# Uno_trung_tam_nha_kinh.net
KiCad netlist of a schematic drawn in Altium Designer
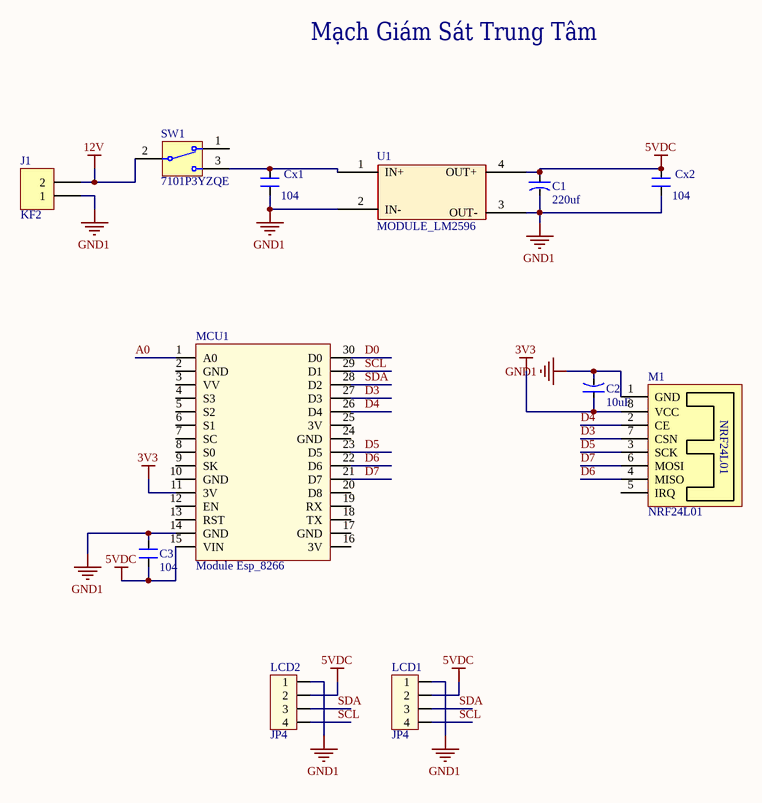
[diagram p0: Uno trung tam nha kinh.SchDoc]

(export (version "E")
  (design (tool "Eeschema 10.0.6"))
  (components
    (comp (ref "C1")
      (value "220uf")
      (footprint "CA-ALU-10R")
      (description "Capacitor (Semiconductor SIM Model)")
      (fields (field (name "PUBLISHER") "Altium Limited"))
      (libsource (lib "LIBRARY") (part "CN-ALU-DIP"))
    )
    (comp (ref "C2")
      (value "10uF")
      (footprint "CA-ALU-6.3R")
      (description "Capacitor (Semiconductor SIM Model)")
      (fields (field (name "PUBLISHER") "Altium Limited"))
      (libsource (lib "LIBRARY") (part "CN-ALU-DIP"))
    )
    (comp (ref "C3") (value "104") (footprint "CN2-T") (libsource (lib "LIBRARY") (part "CN")))
    (comp (ref "Cx1") (value "104") (footprint "CN2-T") (libsource (lib "LIBRARY") (part "CN")))
    (comp (ref "Cx2") (value "104") (footprint "CN2-T") (libsource (lib "LIBRARY") (part "CN")))
    (comp (ref "J1")
      (value "KF2")
      (footprint "KF2-5.08")
      (fields
        (field (name "MANUFACTURER") "Würth Elektronik eiSos GmbH")
        (field (name "PARTNO") "691103110002")
        (field (name "CREATED BY") "Karrer Zheng")
      )
      (libsource (lib "LIBRARY") (part "KF2"))
    )
    (comp (ref "LCD1")
      (value "JP4")
      (footprint "CON4")
      (description "Connector 4")
      (libsource (lib "syhaunguyen") (part "Con4"))
    )
    (comp (ref "LCD2")
      (value "JP4")
      (footprint "CON4")
      (description "Connector 4")
      (libsource (lib "syhaunguyen") (part "Con4"))
    )
    (comp (ref "M1") (value "NRF24L01") (footprint "NRF24L01") (libsource (lib "LIBRARY") (part "NRF24L01")))
    (comp (ref "MCU1")
      (value "Module Esp_8266")
      (footprint "BaDinh_Library:Esp8266_NodeMCU_CP2102")
      (libsource (lib "BaDinh_Library") (part "Module Esp_8266"))
    )
    (comp (ref "SW1")
      (value "7101P3YZQE")
      (footprint "SW_TOGGLE_7101P3YZQE")
      (description "SWITCH TOGGLE SPDT 5A 120V")
      (fields (field (name "MANUFACTURER") "C&K"))
      (libsource (lib "Indruino") (part "SW_TOGGLE_7101P3YZQE"))
    )
    (comp (ref "U1")
      (value "MODULE_LM2596")
      (footprint "BaDinh_Library:MODULE_LM2596")
      (libsource (lib "BaDinh_Library") (part "MODULE_LM2596"))
    )
  )
  (nets
    (net (code "1") (name "/A0") (class "Default")
      (node (ref "MCU1") (pin "1") (pinfunction "A0_1") (pintype "passive"))
    )
    (net (code "2") (name "/D0") (class "Default")
      (node (ref "MCU1") (pin "30") (pinfunction "D0_30") (pintype "passive"))
    )
    (net (code "3") (name "/D3") (class "Default")
      (node (ref "M1") (pin "7") (pinfunction "CSN_7") (pintype "passive"))
      (node (ref "MCU1") (pin "27") (pinfunction "D3_27") (pintype "passive"))
    )
    (net (code "4") (name "/D4") (class "Default")
      (node (ref "M1") (pin "2") (pinfunction "CE_2") (pintype "passive"))
      (node (ref "MCU1") (pin "26") (pinfunction "D4_26") (pintype "passive"))
    )
    (net (code "5") (name "/D5") (class "Default")
      (node (ref "M1") (pin "3") (pinfunction "SCK_3") (pintype "passive"))
      (node (ref "MCU1") (pin "23") (pinfunction "D5_23") (pintype "passive"))
    )
    (net (code "6") (name "/D6") (class "Default")
      (node (ref "M1") (pin "4") (pinfunction "MISO_4") (pintype "passive"))
      (node (ref "MCU1") (pin "22") (pinfunction "D6_22") (pintype "passive"))
    )
    (net (code "7") (name "/D7") (class "Default")
      (node (ref "M1") (pin "6") (pinfunction "MOSI_6") (pintype "passive"))
      (node (ref "MCU1") (pin "21") (pinfunction "D7_21") (pintype "passive"))
    )
    (net (code "8") (name "/SCL") (class "Default")
      (node (ref "LCD1") (pin "4") (pinfunction "4_4") (pintype "passive"))
      (node (ref "LCD2") (pin "4") (pinfunction "4_4") (pintype "passive"))
      (node (ref "MCU1") (pin "29") (pinfunction "D1_29") (pintype "passive"))
    )
    (net (code "9") (name "/SDA") (class "Default")
      (node (ref "LCD1") (pin "3") (pinfunction "3_3") (pintype "passive"))
      (node (ref "LCD2") (pin "3") (pinfunction "3_3") (pintype "passive"))
      (node (ref "MCU1") (pin "28") (pinfunction "D2_28") (pintype "passive"))
    )
    (net (code "10") (name "3V3") (class "Default")
      (node (ref "C2") (pin "1") (pinfunction "1_1") (pintype "passive"))
      (node (ref "M1") (pin "8") (pinfunction "VCC_8") (pintype "passive"))
      (node (ref "MCU1") (pin "11") (pinfunction "3V_11") (pintype "passive"))
    )
    (net (code "11") (name "5VDC") (class "Default")
      (node (ref "C1") (pin "1") (pinfunction "1_1") (pintype "passive"))
      (node (ref "C3") (pin "1") (pinfunction "1_1") (pintype "passive"))
      (node (ref "Cx2") (pin "2") (pinfunction "2_2") (pintype "passive"))
      (node (ref "LCD1") (pin "2") (pinfunction "2_2") (pintype "passive"))
      (node (ref "LCD2") (pin "2") (pinfunction "2_2") (pintype "passive"))
      (node (ref "MCU1") (pin "15") (pinfunction "VIN_15") (pintype "passive"))
      (node (ref "U1") (pin "4") (pinfunction "OUT+_4") (pintype "passive"))
    )
    (net (code "12") (name "12V") (class "Default")
      (node (ref "J1") (pin "2") (pinfunction "2_2") (pintype "passive"))
      (node (ref "SW1") (pin "2") (pinfunction "COM_2") (pintype "passive"))
    )
    (net (code "13") (name "GND1") (class "Default")
      (node (ref "C1") (pin "2") (pinfunction "2_2") (pintype "passive"))
      (node (ref "C2") (pin "2") (pinfunction "2_2") (pintype "passive"))
      (node (ref "C3") (pin "2") (pinfunction "2_2") (pintype "passive"))
      (node (ref "Cx1") (pin "1") (pinfunction "1_1") (pintype "passive"))
      (node (ref "Cx2") (pin "1") (pinfunction "1_1") (pintype "passive"))
      (node (ref "J1") (pin "1") (pinfunction "1_1") (pintype "passive"))
      (node (ref "LCD1") (pin "1") (pinfunction "1_1") (pintype "passive"))
      (node (ref "LCD2") (pin "1") (pinfunction "1_1") (pintype "passive"))
      (node (ref "M1") (pin "1") (pinfunction "GND_1") (pintype "passive"))
      (node (ref "MCU1") (pin "14") (pinfunction "GND_14") (pintype "passive"))
      (node (ref "U1") (pin "2") (pinfunction "IN-_2") (pintype "passive"))
      (node (ref "U1") (pin "3") (pinfunction "OUT-_3") (pintype "passive"))
    )
    (net (code "14") (name "Net-(SW1-NO)") (class "Default")
      (node (ref "Cx1") (pin "2") (pinfunction "2_2") (pintype "passive"))
      (node (ref "SW1") (pin "3") (pinfunction "NO_3") (pintype "passive"))
      (node (ref "U1") (pin "1") (pinfunction "IN+_1") (pintype "passive"))
    )
    (net (code "15") (name "unconnected-(M1-IRQ-Pad5)") (class "Default")
      (node (ref "M1") (pin "5") (pinfunction "IRQ_5") (pintype "passive"))
    )
    (net (code "16") (name "unconnected-(MCU1-3V-Pad16)") (class "Default")
      (node (ref "MCU1") (pin "16") (pinfunction "3V_16") (pintype "passive"))
    )
    (net (code "17") (name "unconnected-(MCU1-3V-Pad25)") (class "Default")
      (node (ref "MCU1") (pin "25") (pinfunction "3V_25") (pintype "passive"))
    )
    (net (code "18") (name "unconnected-(MCU1-D8-Pad20)") (class "Default")
      (node (ref "MCU1") (pin "20") (pinfunction "D8_20") (pintype "passive"))
    )
    (net (code "19") (name "unconnected-(MCU1-EN-Pad12)") (class "Default")
      (node (ref "MCU1") (pin "12") (pinfunction "EN_12") (pintype "passive"))
    )
    (net (code "20") (name "unconnected-(MCU1-GND-Pad2)") (class "Default")
      (node (ref "MCU1") (pin "2") (pinfunction "GND_2") (pintype "passive"))
    )
    (net (code "21") (name "unconnected-(MCU1-GND-Pad10)") (class "Default")
      (node (ref "MCU1") (pin "10") (pinfunction "GND_10") (pintype "passive"))
    )
    (net (code "22") (name "unconnected-(MCU1-GND-Pad17)") (class "Default")
      (node (ref "MCU1") (pin "17") (pinfunction "GND_17") (pintype "passive"))
    )
    (net (code "23") (name "unconnected-(MCU1-GND-Pad24)") (class "Default")
      (node (ref "MCU1") (pin "24") (pinfunction "GND_24") (pintype "passive"))
    )
    (net (code "24") (name "unconnected-(MCU1-RST-Pad13)") (class "Default")
      (node (ref "MCU1") (pin "13") (pinfunction "RST_13") (pintype "passive"))
    )
    (net (code "25") (name "unconnected-(MCU1-RX-Pad19)") (class "Default")
      (node (ref "MCU1") (pin "19") (pinfunction "RX_19") (pintype "passive"))
    )
    (net (code "26") (name "unconnected-(MCU1-S0-Pad8)") (class "Default")
      (node (ref "MCU1") (pin "8") (pinfunction "S0_8") (pintype "passive"))
    )
    (net (code "27") (name "unconnected-(MCU1-S1-Pad6)") (class "Default")
      (node (ref "MCU1") (pin "6") (pinfunction "S1_6") (pintype "passive"))
    )
    (net (code "28") (name "unconnected-(MCU1-S2-Pad5)") (class "Default")
      (node (ref "MCU1") (pin "5") (pinfunction "S2_5") (pintype "passive"))
    )
    (net (code "29") (name "unconnected-(MCU1-S3-Pad4)") (class "Default")
      (node (ref "MCU1") (pin "4") (pinfunction "S3_4") (pintype "passive"))
    )
    (net (code "30") (name "unconnected-(MCU1-SC-Pad7)") (class "Default")
      (node (ref "MCU1") (pin "7") (pinfunction "SC_7") (pintype "passive"))
    )
    (net (code "31") (name "unconnected-(MCU1-SK-Pad9)") (class "Default")
      (node (ref "MCU1") (pin "9") (pinfunction "SK_9") (pintype "passive"))
    )
    (net (code "32") (name "unconnected-(MCU1-TX-Pad18)") (class "Default")
      (node (ref "MCU1") (pin "18") (pinfunction "TX_18") (pintype "passive"))
    )
    (net (code "33") (name "unconnected-(MCU1-VV-Pad3)") (class "Default")
      (node (ref "MCU1") (pin "3") (pinfunction "VV_3") (pintype "passive"))
    )
    (net (code "34") (name "unconnected-(SW1-NC-Pad1)") (class "Default")
      (node (ref "SW1") (pin "1") (pinfunction "NC_1") (pintype "passive"))
    )
  )
)
